# ADC_0_MUL.net
KiCad netlist of a schematic drawn in Altium Designer
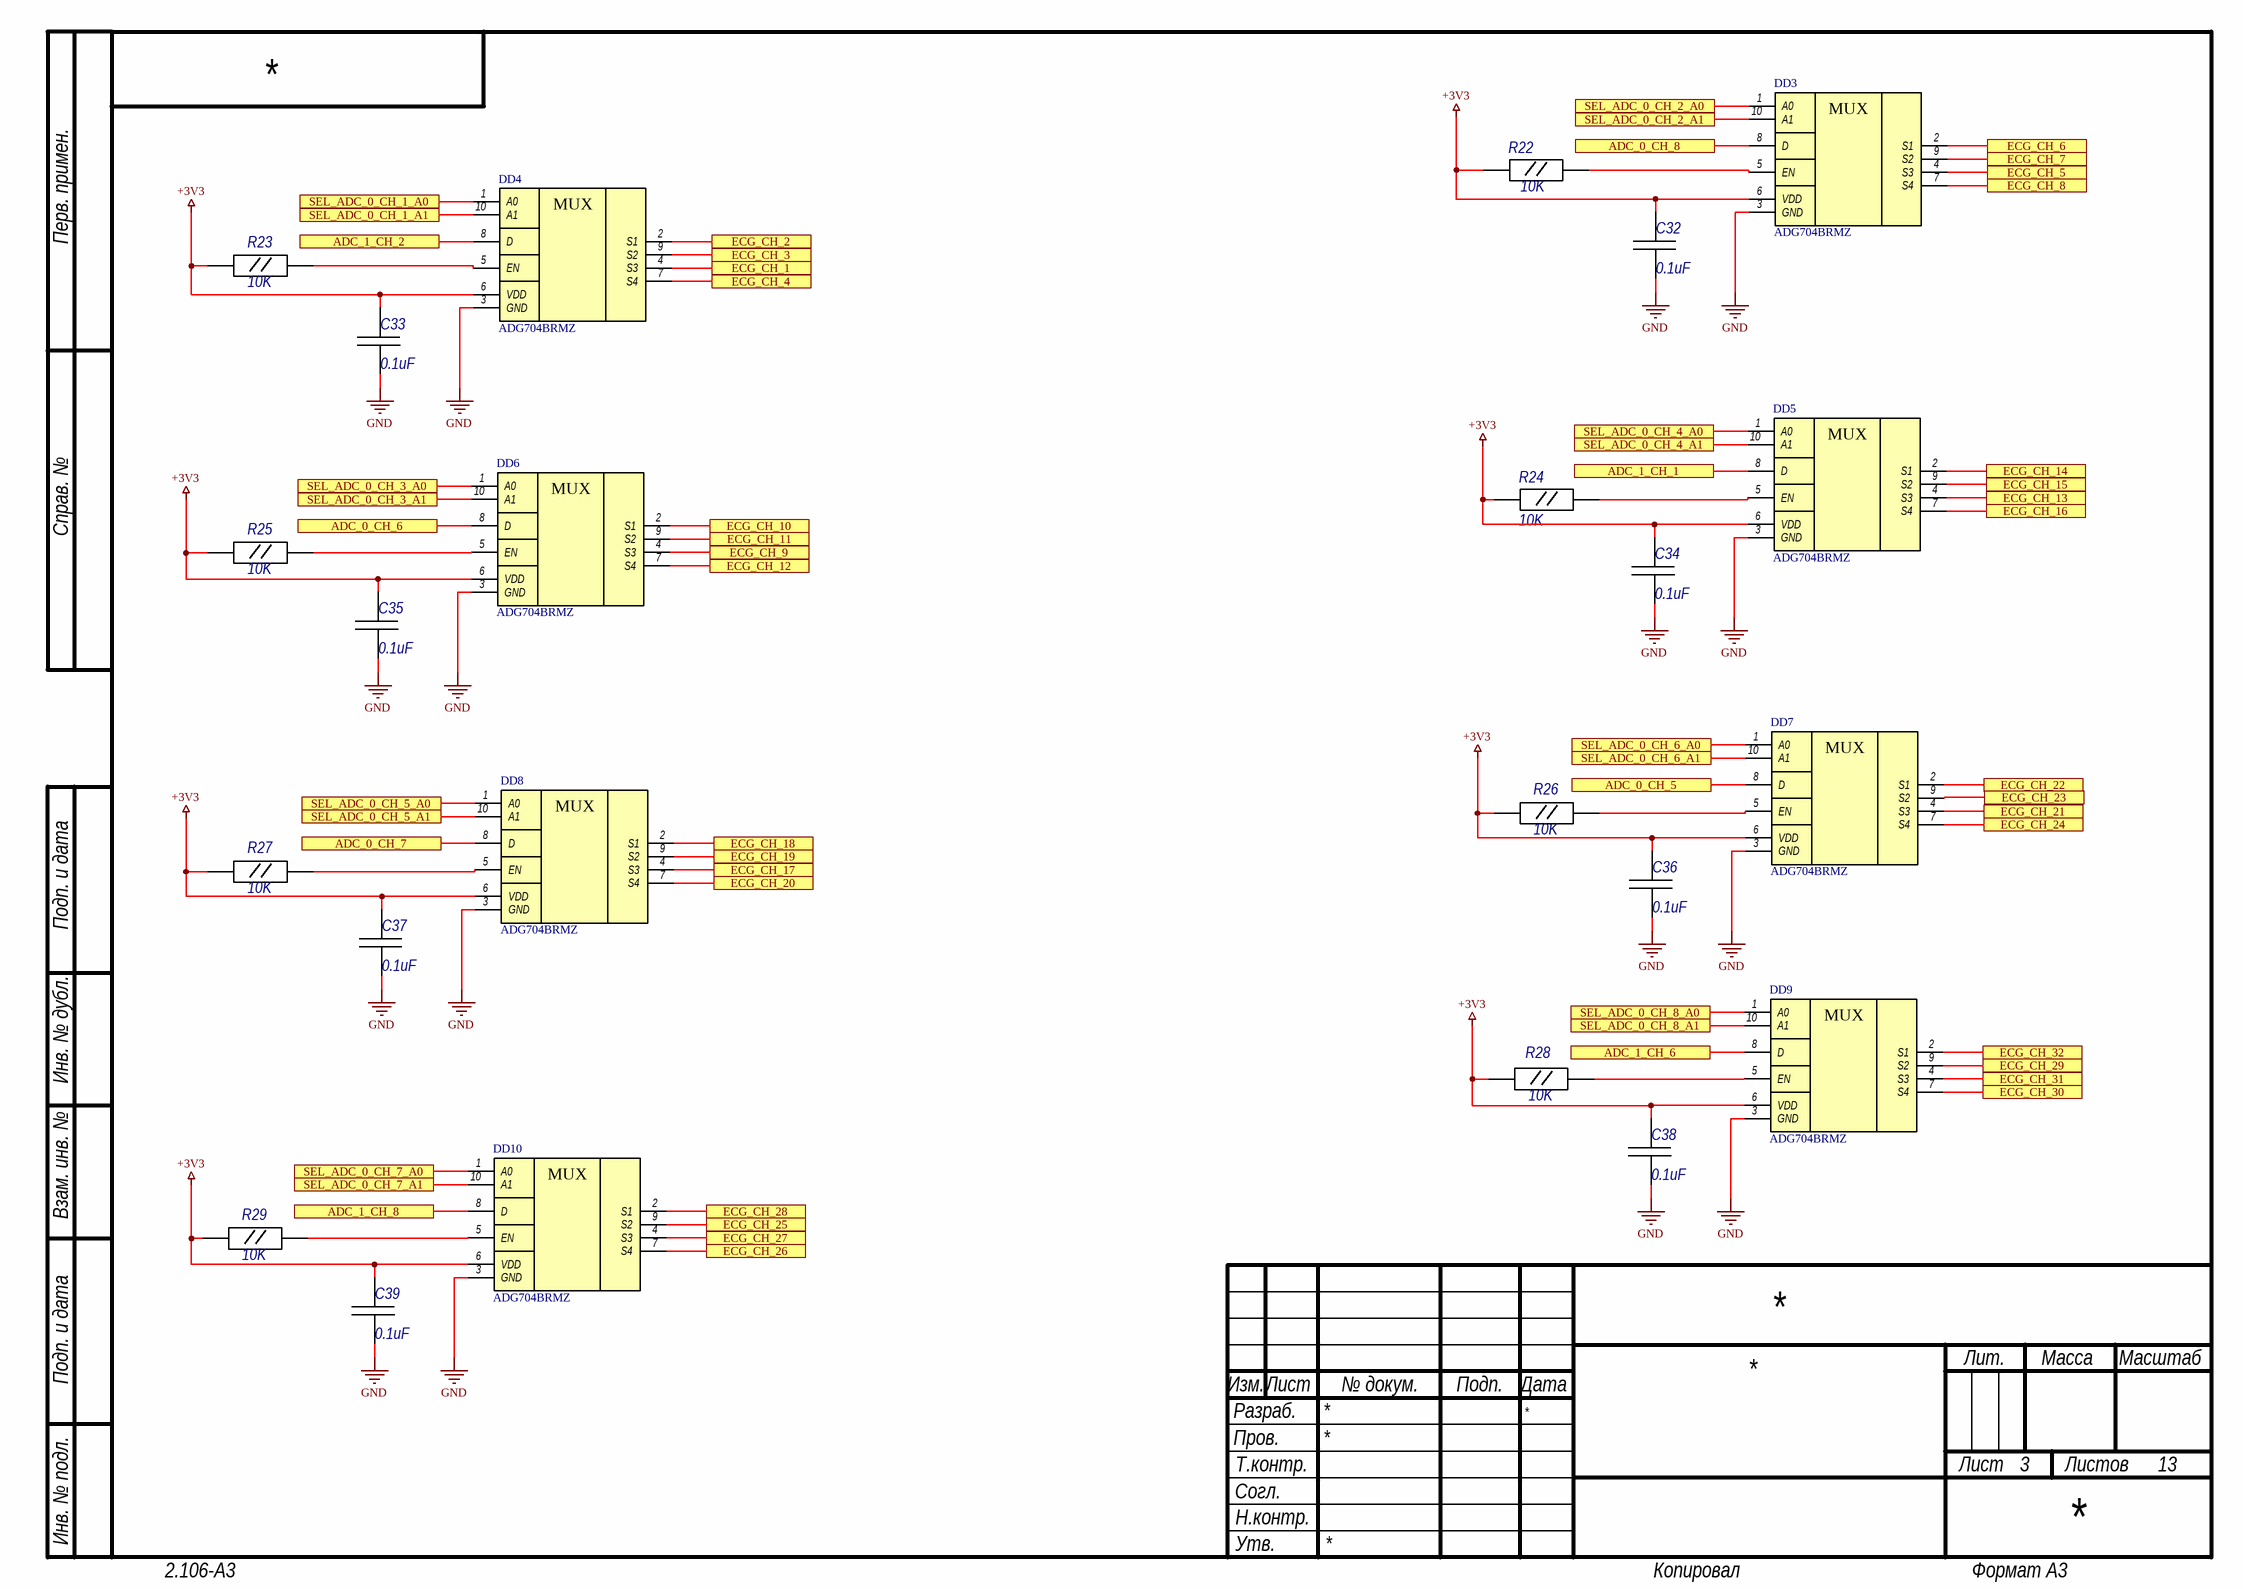
[diagram p0: ADC_0_MUL.SchDoc]

(export (version "E")
  (design (tool "Eeschema 10.0.6"))
  (components
    (comp (ref "C32")
      (value "0.1uF")
      (footprint "C0603")
      (description "Ceramic Capacitor SMD")
      (libsource (lib "GOST") (part "CC_SMD_0603"))
    )
    (comp (ref "C33")
      (value "0.1uF")
      (footprint "C0603")
      (description "Ceramic Capacitor SMD")
      (libsource (lib "GOST") (part "CC_SMD_0603"))
    )
    (comp (ref "C34")
      (value "0.1uF")
      (footprint "C0603")
      (description "Ceramic Capacitor SMD")
      (libsource (lib "GOST") (part "CC_SMD_0603"))
    )
    (comp (ref "C35")
      (value "0.1uF")
      (footprint "C0603")
      (description "Ceramic Capacitor SMD")
      (libsource (lib "GOST") (part "CC_SMD_0603"))
    )
    (comp (ref "C36")
      (value "0.1uF")
      (footprint "C0603")
      (description "Ceramic Capacitor SMD")
      (libsource (lib "GOST") (part "CC_SMD_0603"))
    )
    (comp (ref "C37")
      (value "0.1uF")
      (footprint "C0603")
      (description "Ceramic Capacitor SMD")
      (libsource (lib "GOST") (part "CC_SMD_0603"))
    )
    (comp (ref "C38")
      (value "0.1uF")
      (footprint "C0603")
      (description "Ceramic Capacitor SMD")
      (libsource (lib "GOST") (part "CC_SMD_0603"))
    )
    (comp (ref "C39")
      (value "0.1uF")
      (footprint "C0603")
      (description "Ceramic Capacitor SMD")
      (libsource (lib "GOST") (part "CC_SMD_0603"))
    )
    (comp (ref "DD3")
      (value "ADG704BRMZ")
      (footprint "MSOP-10")
      (description "4-Channel Multiplexer")
      (libsource (lib "GOST") (part "MUX_ADG704BRMZ"))
    )
    (comp (ref "DD4")
      (value "ADG704BRMZ")
      (footprint "MSOP-10")
      (description "4-Channel Multiplexer")
      (libsource (lib "GOST") (part "MUX_ADG704BRMZ"))
    )
    (comp (ref "DD5")
      (value "ADG704BRMZ")
      (footprint "MSOP-10")
      (description "4-Channel Multiplexer")
      (libsource (lib "GOST") (part "MUX_ADG704BRMZ"))
    )
    (comp (ref "DD6")
      (value "ADG704BRMZ")
      (footprint "MSOP-10")
      (description "4-Channel Multiplexer")
      (libsource (lib "GOST") (part "MUX_ADG704BRMZ"))
    )
    (comp (ref "DD7")
      (value "ADG704BRMZ")
      (footprint "MSOP-10")
      (description "4-Channel Multiplexer")
      (libsource (lib "GOST") (part "MUX_ADG704BRMZ"))
    )
    (comp (ref "DD8")
      (value "ADG704BRMZ")
      (footprint "MSOP-10")
      (description "4-Channel Multiplexer")
      (libsource (lib "GOST") (part "MUX_ADG704BRMZ"))
    )
    (comp (ref "DD9")
      (value "ADG704BRMZ")
      (footprint "MSOP-10")
      (description "4-Channel Multiplexer")
      (libsource (lib "GOST") (part "MUX_ADG704BRMZ"))
    )
    (comp (ref "DD10")
      (value "ADG704BRMZ")
      (footprint "MSOP-10")
      (description "4-Channel Multiplexer")
      (libsource (lib "GOST") (part "MUX_ADG704BRMZ"))
    )
    (comp (ref "R22")
      (value "10K")
      (footprint "R0603")
      (description "Resistor SMD")
      (libsource (lib "GOST") (part "R0603"))
    )
    (comp (ref "R23")
      (value "10K")
      (footprint "R0603")
      (description "Resistor SMD")
      (libsource (lib "") (part "R0603_1"))
    )
    (comp (ref "R24")
      (value "10K")
      (footprint "R0603")
      (description "Resistor SMD")
      (libsource (lib "GOST") (part "R0603"))
    )
    (comp (ref "R25")
      (value "10K")
      (footprint "R0603")
      (description "Resistor SMD")
      (libsource (lib "") (part "R0603_1"))
    )
    (comp (ref "R26")
      (value "10K")
      (footprint "R0603")
      (description "Resistor SMD")
      (libsource (lib "GOST") (part "R0603"))
    )
    (comp (ref "R27")
      (value "10K")
      (footprint "R0603")
      (description "Resistor SMD")
      (libsource (lib "") (part "R0603_1"))
    )
    (comp (ref "R28")
      (value "10K")
      (footprint "R0603")
      (description "Resistor SMD")
      (libsource (lib "GOST") (part "R0603"))
    )
    (comp (ref "R29")
      (value "10K")
      (footprint "R0603")
      (description "Resistor SMD")
      (libsource (lib "") (part "R0603_1"))
    )
  )
  (nets
    (net (code "1") (name "+3V3") (class "Default")
      (node (ref "C32") (pin "2") (pinfunction "2_2") (pintype "passive"))
      (node (ref "C33") (pin "2") (pinfunction "2_2") (pintype "passive"))
      (node (ref "C34") (pin "2") (pinfunction "2_2") (pintype "passive"))
      (node (ref "C35") (pin "2") (pinfunction "2_2") (pintype "passive"))
      (node (ref "C36") (pin "2") (pinfunction "2_2") (pintype "passive"))
      (node (ref "C37") (pin "2") (pinfunction "2_2") (pintype "passive"))
      (node (ref "C38") (pin "2") (pinfunction "2_2") (pintype "passive"))
      (node (ref "C39") (pin "2") (pinfunction "2_2") (pintype "passive"))
      (node (ref "DD10") (pin "6") (pinfunction "VDD_6") (pintype "passive"))
      (node (ref "DD3") (pin "6") (pinfunction "VDD_6") (pintype "passive"))
      (node (ref "DD4") (pin "6") (pinfunction "VDD_6") (pintype "passive"))
      (node (ref "DD5") (pin "6") (pinfunction "VDD_6") (pintype "passive"))
      (node (ref "DD6") (pin "6") (pinfunction "VDD_6") (pintype "passive"))
      (node (ref "DD7") (pin "6") (pinfunction "VDD_6") (pintype "passive"))
      (node (ref "DD8") (pin "6") (pinfunction "VDD_6") (pintype "passive"))
      (node (ref "DD9") (pin "6") (pinfunction "VDD_6") (pintype "passive"))
      (node (ref "R22") (pin "1") (pinfunction "1_1") (pintype "passive"))
      (node (ref "R23") (pin "1") (pinfunction "1_1") (pintype "passive"))
      (node (ref "R24") (pin "1") (pinfunction "1_1") (pintype "passive"))
      (node (ref "R25") (pin "1") (pinfunction "1_1") (pintype "passive"))
      (node (ref "R26") (pin "1") (pinfunction "1_1") (pintype "passive"))
      (node (ref "R27") (pin "1") (pinfunction "1_1") (pintype "passive"))
      (node (ref "R28") (pin "1") (pinfunction "1_1") (pintype "passive"))
      (node (ref "R29") (pin "1") (pinfunction "1_1") (pintype "passive"))
    )
    (net (code "2") (name "/ADC_0_CH_5") (class "Default")
      (node (ref "DD7") (pin "8") (pinfunction "D_8") (pintype "passive"))
    )
    (net (code "3") (name "/ADC_0_CH_6") (class "Default")
      (node (ref "DD6") (pin "8") (pinfunction "D_8") (pintype "passive"))
    )
    (net (code "4") (name "/ADC_0_CH_7") (class "Default")
      (node (ref "DD8") (pin "8") (pinfunction "D_8") (pintype "passive"))
    )
    (net (code "5") (name "/ADC_0_CH_8") (class "Default")
      (node (ref "DD3") (pin "8") (pinfunction "D_8") (pintype "passive"))
    )
    (net (code "6") (name "/ADC_1_CH_1") (class "Default")
      (node (ref "DD5") (pin "8") (pinfunction "D_8") (pintype "passive"))
    )
    (net (code "7") (name "/ADC_1_CH_2") (class "Default")
      (node (ref "DD4") (pin "8") (pinfunction "D_8") (pintype "passive"))
    )
    (net (code "8") (name "/ADC_1_CH_6") (class "Default")
      (node (ref "DD9") (pin "8") (pinfunction "D_8") (pintype "passive"))
    )
    (net (code "9") (name "/ADC_1_CH_8") (class "Default")
      (node (ref "DD10") (pin "8") (pinfunction "D_8") (pintype "passive"))
    )
    (net (code "10") (name "/ECG_CH_1") (class "Default")
      (node (ref "DD4") (pin "4") (pinfunction "S3_4") (pintype "passive"))
    )
    (net (code "11") (name "/ECG_CH_2") (class "Default")
      (node (ref "DD4") (pin "2") (pinfunction "S1_2") (pintype "passive"))
    )
    (net (code "12") (name "/ECG_CH_3") (class "Default")
      (node (ref "DD4") (pin "9") (pinfunction "S2_9") (pintype "passive"))
    )
    (net (code "13") (name "/ECG_CH_4") (class "Default")
      (node (ref "DD4") (pin "7") (pinfunction "S4_7") (pintype "passive"))
    )
    (net (code "14") (name "/ECG_CH_5") (class "Default")
      (node (ref "DD3") (pin "4") (pinfunction "S3_4") (pintype "passive"))
    )
    (net (code "15") (name "/ECG_CH_6") (class "Default")
      (node (ref "DD3") (pin "2") (pinfunction "S1_2") (pintype "passive"))
    )
    (net (code "16") (name "/ECG_CH_7") (class "Default")
      (node (ref "DD3") (pin "9") (pinfunction "S2_9") (pintype "passive"))
    )
    (net (code "17") (name "/ECG_CH_8") (class "Default")
      (node (ref "DD3") (pin "7") (pinfunction "S4_7") (pintype "passive"))
    )
    (net (code "18") (name "/ECG_CH_9") (class "Default")
      (node (ref "DD6") (pin "4") (pinfunction "S3_4") (pintype "passive"))
    )
    (net (code "19") (name "/ECG_CH_10") (class "Default")
      (node (ref "DD6") (pin "2") (pinfunction "S1_2") (pintype "passive"))
    )
    (net (code "20") (name "/ECG_CH_11") (class "Default")
      (node (ref "DD6") (pin "9") (pinfunction "S2_9") (pintype "passive"))
    )
    (net (code "21") (name "/ECG_CH_12") (class "Default")
      (node (ref "DD6") (pin "7") (pinfunction "S4_7") (pintype "passive"))
    )
    (net (code "22") (name "/ECG_CH_13") (class "Default")
      (node (ref "DD5") (pin "4") (pinfunction "S3_4") (pintype "passive"))
    )
    (net (code "23") (name "/ECG_CH_14") (class "Default")
      (node (ref "DD5") (pin "2") (pinfunction "S1_2") (pintype "passive"))
    )
    (net (code "24") (name "/ECG_CH_15") (class "Default")
      (node (ref "DD5") (pin "9") (pinfunction "S2_9") (pintype "passive"))
    )
    (net (code "25") (name "/ECG_CH_16") (class "Default")
      (node (ref "DD5") (pin "7") (pinfunction "S4_7") (pintype "passive"))
    )
    (net (code "26") (name "/ECG_CH_17") (class "Default")
      (node (ref "DD8") (pin "4") (pinfunction "S3_4") (pintype "passive"))
    )
    (net (code "27") (name "/ECG_CH_18") (class "Default")
      (node (ref "DD8") (pin "2") (pinfunction "S1_2") (pintype "passive"))
    )
    (net (code "28") (name "/ECG_CH_19") (class "Default")
      (node (ref "DD8") (pin "9") (pinfunction "S2_9") (pintype "passive"))
    )
    (net (code "29") (name "/ECG_CH_20") (class "Default")
      (node (ref "DD8") (pin "7") (pinfunction "S4_7") (pintype "passive"))
    )
    (net (code "30") (name "/ECG_CH_21") (class "Default")
      (node (ref "DD7") (pin "4") (pinfunction "S3_4") (pintype "passive"))
    )
    (net (code "31") (name "/ECG_CH_22") (class "Default")
      (node (ref "DD7") (pin "2") (pinfunction "S1_2") (pintype "passive"))
    )
    (net (code "32") (name "/ECG_CH_23") (class "Default")
      (node (ref "DD7") (pin "9") (pinfunction "S2_9") (pintype "passive"))
    )
    (net (code "33") (name "/ECG_CH_24") (class "Default")
      (node (ref "DD7") (pin "7") (pinfunction "S4_7") (pintype "passive"))
    )
    (net (code "34") (name "/ECG_CH_25") (class "Default")
      (node (ref "DD10") (pin "9") (pinfunction "S2_9") (pintype "passive"))
    )
    (net (code "35") (name "/ECG_CH_26") (class "Default")
      (node (ref "DD10") (pin "7") (pinfunction "S4_7") (pintype "passive"))
    )
    (net (code "36") (name "/ECG_CH_27") (class "Default")
      (node (ref "DD10") (pin "4") (pinfunction "S3_4") (pintype "passive"))
    )
    (net (code "37") (name "/ECG_CH_28") (class "Default")
      (node (ref "DD10") (pin "2") (pinfunction "S1_2") (pintype "passive"))
    )
    (net (code "38") (name "/ECG_CH_29") (class "Default")
      (node (ref "DD9") (pin "9") (pinfunction "S2_9") (pintype "passive"))
    )
    (net (code "39") (name "/ECG_CH_30") (class "Default")
      (node (ref "DD9") (pin "7") (pinfunction "S4_7") (pintype "passive"))
    )
    (net (code "40") (name "/ECG_CH_31") (class "Default")
      (node (ref "DD9") (pin "4") (pinfunction "S3_4") (pintype "passive"))
    )
    (net (code "41") (name "/ECG_CH_32") (class "Default")
      (node (ref "DD9") (pin "2") (pinfunction "S1_2") (pintype "passive"))
    )
    (net (code "42") (name "/SEL_ADC_0_CH_1_A0") (class "Default")
      (node (ref "DD4") (pin "1") (pinfunction "A0_1") (pintype "passive"))
    )
    (net (code "43") (name "/SEL_ADC_0_CH_1_A1") (class "Default")
      (node (ref "DD4") (pin "10") (pinfunction "A1_10") (pintype "passive"))
    )
    (net (code "44") (name "/SEL_ADC_0_CH_2_A0") (class "Default")
      (node (ref "DD3") (pin "1") (pinfunction "A0_1") (pintype "passive"))
    )
    (net (code "45") (name "/SEL_ADC_0_CH_2_A1") (class "Default")
      (node (ref "DD3") (pin "10") (pinfunction "A1_10") (pintype "passive"))
    )
    (net (code "46") (name "/SEL_ADC_0_CH_3_A0") (class "Default")
      (node (ref "DD6") (pin "1") (pinfunction "A0_1") (pintype "passive"))
    )
    (net (code "47") (name "/SEL_ADC_0_CH_3_A1") (class "Default")
      (node (ref "DD6") (pin "10") (pinfunction "A1_10") (pintype "passive"))
    )
    (net (code "48") (name "/SEL_ADC_0_CH_4_A0") (class "Default")
      (node (ref "DD5") (pin "1") (pinfunction "A0_1") (pintype "passive"))
    )
    (net (code "49") (name "/SEL_ADC_0_CH_4_A1") (class "Default")
      (node (ref "DD5") (pin "10") (pinfunction "A1_10") (pintype "passive"))
    )
    (net (code "50") (name "/SEL_ADC_0_CH_5_A0") (class "Default")
      (node (ref "DD8") (pin "1") (pinfunction "A0_1") (pintype "passive"))
    )
    (net (code "51") (name "/SEL_ADC_0_CH_5_A1") (class "Default")
      (node (ref "DD8") (pin "10") (pinfunction "A1_10") (pintype "passive"))
    )
    (net (code "52") (name "/SEL_ADC_0_CH_6_A0") (class "Default")
      (node (ref "DD7") (pin "1") (pinfunction "A0_1") (pintype "passive"))
    )
    (net (code "53") (name "/SEL_ADC_0_CH_6_A1") (class "Default")
      (node (ref "DD7") (pin "10") (pinfunction "A1_10") (pintype "passive"))
    )
    (net (code "54") (name "/SEL_ADC_0_CH_7_A0") (class "Default")
      (node (ref "DD10") (pin "1") (pinfunction "A0_1") (pintype "passive"))
    )
    (net (code "55") (name "/SEL_ADC_0_CH_7_A1") (class "Default")
      (node (ref "DD10") (pin "10") (pinfunction "A1_10") (pintype "passive"))
    )
    (net (code "56") (name "/SEL_ADC_0_CH_8_A0") (class "Default")
      (node (ref "DD9") (pin "1") (pinfunction "A0_1") (pintype "passive"))
    )
    (net (code "57") (name "/SEL_ADC_0_CH_8_A1") (class "Default")
      (node (ref "DD9") (pin "10") (pinfunction "A1_10") (pintype "passive"))
    )
    (net (code "58") (name "GND") (class "Default")
      (node (ref "C32") (pin "1") (pinfunction "1_1") (pintype "passive"))
      (node (ref "C33") (pin "1") (pinfunction "1_1") (pintype "passive"))
      (node (ref "C34") (pin "1") (pinfunction "1_1") (pintype "passive"))
      (node (ref "C35") (pin "1") (pinfunction "1_1") (pintype "passive"))
      (node (ref "C36") (pin "1") (pinfunction "1_1") (pintype "passive"))
      (node (ref "C37") (pin "1") (pinfunction "1_1") (pintype "passive"))
      (node (ref "C38") (pin "1") (pinfunction "1_1") (pintype "passive"))
      (node (ref "C39") (pin "1") (pinfunction "1_1") (pintype "passive"))
      (node (ref "DD10") (pin "3") (pinfunction "GND_3") (pintype "passive"))
      (node (ref "DD3") (pin "3") (pinfunction "GND_3") (pintype "passive"))
      (node (ref "DD4") (pin "3") (pinfunction "GND_3") (pintype "passive"))
      (node (ref "DD5") (pin "3") (pinfunction "GND_3") (pintype "passive"))
      (node (ref "DD6") (pin "3") (pinfunction "GND_3") (pintype "passive"))
      (node (ref "DD7") (pin "3") (pinfunction "GND_3") (pintype "passive"))
      (node (ref "DD8") (pin "3") (pinfunction "GND_3") (pintype "passive"))
      (node (ref "DD9") (pin "3") (pinfunction "GND_3") (pintype "passive"))
    )
    (net (code "59") (name "Net-(DD3-EN)") (class "Default")
      (node (ref "DD3") (pin "5") (pinfunction "EN_5") (pintype "passive"))
      (node (ref "R22") (pin "2") (pinfunction "2_2") (pintype "passive"))
    )
    (net (code "60") (name "Net-(DD4-EN)") (class "Default")
      (node (ref "DD4") (pin "5") (pinfunction "EN_5") (pintype "passive"))
      (node (ref "R23") (pin "2") (pinfunction "2_2") (pintype "passive"))
    )
    (net (code "61") (name "Net-(DD5-EN)") (class "Default")
      (node (ref "DD5") (pin "5") (pinfunction "EN_5") (pintype "passive"))
      (node (ref "R24") (pin "2") (pinfunction "2_2") (pintype "passive"))
    )
    (net (code "62") (name "Net-(DD6-EN)") (class "Default")
      (node (ref "DD6") (pin "5") (pinfunction "EN_5") (pintype "passive"))
      (node (ref "R25") (pin "2") (pinfunction "2_2") (pintype "passive"))
    )
    (net (code "63") (name "Net-(DD7-EN)") (class "Default")
      (node (ref "DD7") (pin "5") (pinfunction "EN_5") (pintype "passive"))
      (node (ref "R26") (pin "2") (pinfunction "2_2") (pintype "passive"))
    )
    (net (code "64") (name "Net-(DD8-EN)") (class "Default")
      (node (ref "DD8") (pin "5") (pinfunction "EN_5") (pintype "passive"))
      (node (ref "R27") (pin "2") (pinfunction "2_2") (pintype "passive"))
    )
    (net (code "65") (name "Net-(DD9-EN)") (class "Default")
      (node (ref "DD9") (pin "5") (pinfunction "EN_5") (pintype "passive"))
      (node (ref "R28") (pin "2") (pinfunction "2_2") (pintype "passive"))
    )
    (net (code "66") (name "Net-(DD10-EN)") (class "Default")
      (node (ref "DD10") (pin "5") (pinfunction "EN_5") (pintype "passive"))
      (node (ref "R29") (pin "2") (pinfunction "2_2") (pintype "passive"))
    )
  )
)
